# B1653P01Main-2.net
KiCad netlist of a schematic drawn in Altium Designer
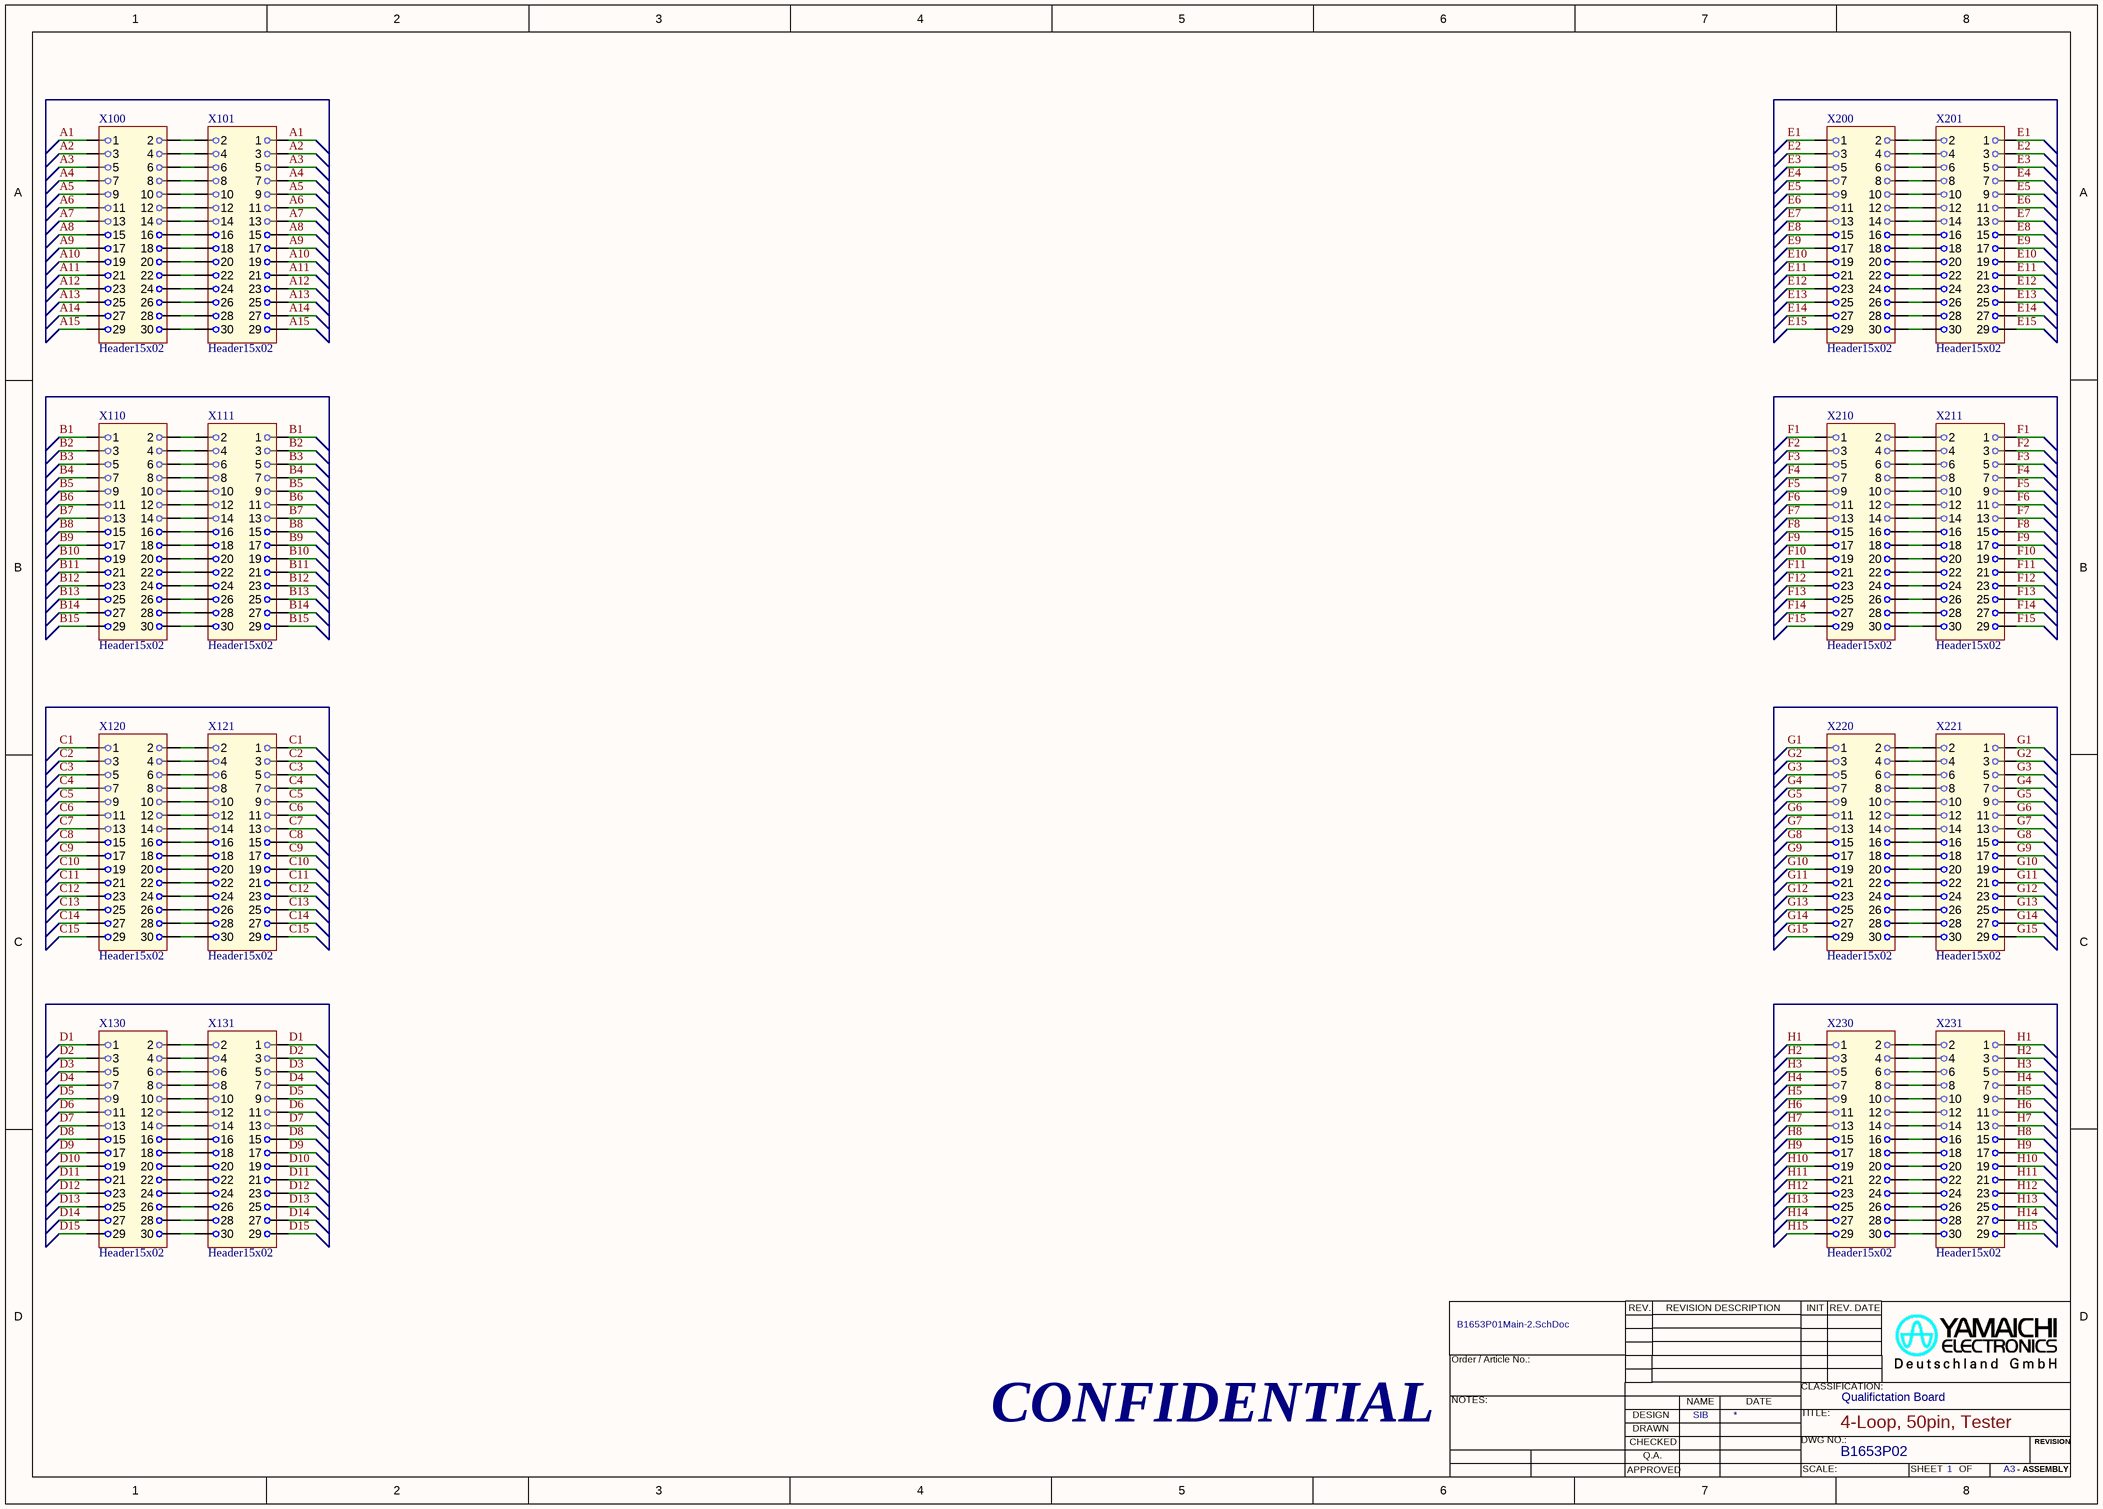
[diagram p0: B1653P01Main-2.SchDoc]

(export (version "E")
  (design (tool "Eeschema 10.0.6"))
  (components
    (comp (ref "X100")
      (value "Header15x02")
      (footprint "HEADER15x02_thru")
      (description "Header15x02 thru")
      (fields (field (name "TYPE") "Header15x02") (field (name "PART NUMBER") "X000027"))
      (libsource (lib "") (part "Header15x02_1"))
    )
    (comp (ref "X101")
      (value "Header15x02")
      (footprint "HEADER15x02_thru")
      (description "Header15x02 thru")
      (fields (field (name "TYPE") "Header15x02") (field (name "PART NUMBER") "X000027"))
      (libsource (lib "X") (part "Header15x02"))
    )
    (comp (ref "X110")
      (value "Header15x02")
      (footprint "HEADER15x02_thru")
      (description "Header15x02 thru")
      (fields (field (name "TYPE") "Header15x02") (field (name "PART NUMBER") "X000027"))
      (libsource (lib "") (part "Header15x02_1"))
    )
    (comp (ref "X111")
      (value "Header15x02")
      (footprint "HEADER15x02_thru")
      (description "Header15x02 thru")
      (fields (field (name "TYPE") "Header15x02") (field (name "PART NUMBER") "X000027"))
      (libsource (lib "X") (part "Header15x02"))
    )
    (comp (ref "X120")
      (value "Header15x02")
      (footprint "HEADER15x02_thru")
      (description "Header15x02 thru")
      (fields (field (name "TYPE") "Header15x02") (field (name "PART NUMBER") "X000027"))
      (libsource (lib "") (part "Header15x02_1"))
    )
    (comp (ref "X121")
      (value "Header15x02")
      (footprint "HEADER15x02_thru")
      (description "Header15x02 thru")
      (fields (field (name "TYPE") "Header15x02") (field (name "PART NUMBER") "X000027"))
      (libsource (lib "X") (part "Header15x02"))
    )
    (comp (ref "X130")
      (value "Header15x02")
      (footprint "HEADER15x02_thru")
      (description "Header15x02 thru")
      (fields (field (name "TYPE") "Header15x02") (field (name "PART NUMBER") "X000027"))
      (libsource (lib "") (part "Header15x02_1"))
    )
    (comp (ref "X131")
      (value "Header15x02")
      (footprint "HEADER15x02_thru")
      (description "Header15x02 thru")
      (fields (field (name "TYPE") "Header15x02") (field (name "PART NUMBER") "X000027"))
      (libsource (lib "X") (part "Header15x02"))
    )
    (comp (ref "X200")
      (value "Header15x02")
      (footprint "HEADER15x02_thru")
      (description "Header15x02 thru")
      (fields (field (name "TYPE") "Header15x02") (field (name "PART NUMBER") "X000027"))
      (libsource (lib "") (part "Header15x02_1"))
    )
    (comp (ref "X201")
      (value "Header15x02")
      (footprint "HEADER15x02_thru")
      (description "Header15x02 thru")
      (fields (field (name "TYPE") "Header15x02") (field (name "PART NUMBER") "X000027"))
      (libsource (lib "X") (part "Header15x02"))
    )
    (comp (ref "X210")
      (value "Header15x02")
      (footprint "HEADER15x02_thru")
      (description "Header15x02 thru")
      (fields (field (name "TYPE") "Header15x02") (field (name "PART NUMBER") "X000027"))
      (libsource (lib "") (part "Header15x02_1"))
    )
    (comp (ref "X211")
      (value "Header15x02")
      (footprint "HEADER15x02_thru")
      (description "Header15x02 thru")
      (fields (field (name "TYPE") "Header15x02") (field (name "PART NUMBER") "X000027"))
      (libsource (lib "X") (part "Header15x02"))
    )
    (comp (ref "X220")
      (value "Header15x02")
      (footprint "HEADER15x02_thru")
      (description "Header15x02 thru")
      (fields (field (name "TYPE") "Header15x02") (field (name "PART NUMBER") "X000027"))
      (libsource (lib "") (part "Header15x02_1"))
    )
    (comp (ref "X221")
      (value "Header15x02")
      (footprint "HEADER15x02_thru")
      (description "Header15x02 thru")
      (fields (field (name "TYPE") "Header15x02") (field (name "PART NUMBER") "X000027"))
      (libsource (lib "X") (part "Header15x02"))
    )
    (comp (ref "X230")
      (value "Header15x02")
      (footprint "HEADER15x02_thru")
      (description "Header15x02 thru")
      (fields (field (name "TYPE") "Header15x02") (field (name "PART NUMBER") "X000027"))
      (libsource (lib "") (part "Header15x02_1"))
    )
    (comp (ref "X231")
      (value "Header15x02")
      (footprint "HEADER15x02_thru")
      (description "Header15x02 thru")
      (fields (field (name "TYPE") "Header15x02") (field (name "PART NUMBER") "X000027"))
      (libsource (lib "X") (part "Header15x02"))
    )
  )
  (nets
    (net (code "1") (name "/A1") (class "Default")
      (node (ref "X100") (pin "1") (pinfunction "1_1") (pintype "passive"))
      (node (ref "X101") (pin "1") (pinfunction "1_1") (pintype "passive"))
    )
    (net (code "2") (name "/A2") (class "Default")
      (node (ref "X100") (pin "3") (pinfunction "3_3") (pintype "passive"))
      (node (ref "X101") (pin "3") (pinfunction "3_3") (pintype "passive"))
    )
    (net (code "3") (name "/A3") (class "Default")
      (node (ref "X100") (pin "5") (pinfunction "5_5") (pintype "passive"))
      (node (ref "X101") (pin "5") (pinfunction "5_5") (pintype "passive"))
    )
    (net (code "4") (name "/A4") (class "Default")
      (node (ref "X100") (pin "7") (pinfunction "7_7") (pintype "passive"))
      (node (ref "X101") (pin "7") (pinfunction "7_7") (pintype "passive"))
    )
    (net (code "5") (name "/A5") (class "Default")
      (node (ref "X100") (pin "9") (pinfunction "9_9") (pintype "passive"))
      (node (ref "X101") (pin "9") (pinfunction "9_9") (pintype "passive"))
    )
    (net (code "6") (name "/A6") (class "Default")
      (node (ref "X100") (pin "11") (pinfunction "11_11") (pintype "passive"))
      (node (ref "X101") (pin "11") (pinfunction "11_11") (pintype "passive"))
    )
    (net (code "7") (name "/A7") (class "Default")
      (node (ref "X100") (pin "13") (pinfunction "13_13") (pintype "passive"))
      (node (ref "X101") (pin "13") (pinfunction "13_13") (pintype "passive"))
    )
    (net (code "8") (name "/A8") (class "Default")
      (node (ref "X100") (pin "15") (pinfunction "15_15") (pintype "passive"))
      (node (ref "X101") (pin "15") (pinfunction "15_15") (pintype "passive"))
    )
    (net (code "9") (name "/A9") (class "Default")
      (node (ref "X100") (pin "17") (pinfunction "17_17") (pintype "passive"))
      (node (ref "X101") (pin "17") (pinfunction "17_17") (pintype "passive"))
    )
    (net (code "10") (name "/A10") (class "Default")
      (node (ref "X100") (pin "19") (pinfunction "19_19") (pintype "passive"))
      (node (ref "X101") (pin "19") (pinfunction "19_19") (pintype "passive"))
    )
    (net (code "11") (name "/A11") (class "Default")
      (node (ref "X100") (pin "21") (pinfunction "21_21") (pintype "passive"))
      (node (ref "X101") (pin "21") (pinfunction "21_21") (pintype "passive"))
    )
    (net (code "12") (name "/A12") (class "Default")
      (node (ref "X100") (pin "23") (pinfunction "23_23") (pintype "passive"))
      (node (ref "X101") (pin "23") (pinfunction "23_23") (pintype "passive"))
    )
    (net (code "13") (name "/A13") (class "Default")
      (node (ref "X100") (pin "25") (pinfunction "25_25") (pintype "passive"))
      (node (ref "X101") (pin "25") (pinfunction "25_25") (pintype "passive"))
    )
    (net (code "14") (name "/A14") (class "Default")
      (node (ref "X100") (pin "27") (pinfunction "27_27") (pintype "passive"))
      (node (ref "X101") (pin "27") (pinfunction "27_27") (pintype "passive"))
    )
    (net (code "15") (name "/A15") (class "Default")
      (node (ref "X100") (pin "29") (pinfunction "29_29") (pintype "passive"))
      (node (ref "X101") (pin "29") (pinfunction "29_29") (pintype "passive"))
    )
    (net (code "16") (name "/B1") (class "Default")
      (node (ref "X110") (pin "1") (pinfunction "1_1") (pintype "passive"))
      (node (ref "X111") (pin "1") (pinfunction "1_1") (pintype "passive"))
    )
    (net (code "17") (name "/B2") (class "Default")
      (node (ref "X110") (pin "3") (pinfunction "3_3") (pintype "passive"))
      (node (ref "X111") (pin "3") (pinfunction "3_3") (pintype "passive"))
    )
    (net (code "18") (name "/B3") (class "Default")
      (node (ref "X110") (pin "5") (pinfunction "5_5") (pintype "passive"))
      (node (ref "X111") (pin "5") (pinfunction "5_5") (pintype "passive"))
    )
    (net (code "19") (name "/B4") (class "Default")
      (node (ref "X110") (pin "7") (pinfunction "7_7") (pintype "passive"))
      (node (ref "X111") (pin "7") (pinfunction "7_7") (pintype "passive"))
    )
    (net (code "20") (name "/B5") (class "Default")
      (node (ref "X110") (pin "9") (pinfunction "9_9") (pintype "passive"))
      (node (ref "X111") (pin "9") (pinfunction "9_9") (pintype "passive"))
    )
    (net (code "21") (name "/B6") (class "Default")
      (node (ref "X110") (pin "11") (pinfunction "11_11") (pintype "passive"))
      (node (ref "X111") (pin "11") (pinfunction "11_11") (pintype "passive"))
    )
    (net (code "22") (name "/B7") (class "Default")
      (node (ref "X110") (pin "13") (pinfunction "13_13") (pintype "passive"))
      (node (ref "X111") (pin "13") (pinfunction "13_13") (pintype "passive"))
    )
    (net (code "23") (name "/B8") (class "Default")
      (node (ref "X110") (pin "15") (pinfunction "15_15") (pintype "passive"))
      (node (ref "X111") (pin "15") (pinfunction "15_15") (pintype "passive"))
    )
    (net (code "24") (name "/B9") (class "Default")
      (node (ref "X110") (pin "17") (pinfunction "17_17") (pintype "passive"))
      (node (ref "X111") (pin "17") (pinfunction "17_17") (pintype "passive"))
    )
    (net (code "25") (name "/B10") (class "Default")
      (node (ref "X110") (pin "19") (pinfunction "19_19") (pintype "passive"))
      (node (ref "X111") (pin "19") (pinfunction "19_19") (pintype "passive"))
    )
    (net (code "26") (name "/B11") (class "Default")
      (node (ref "X110") (pin "21") (pinfunction "21_21") (pintype "passive"))
      (node (ref "X111") (pin "21") (pinfunction "21_21") (pintype "passive"))
    )
    (net (code "27") (name "/B12") (class "Default")
      (node (ref "X110") (pin "23") (pinfunction "23_23") (pintype "passive"))
      (node (ref "X111") (pin "23") (pinfunction "23_23") (pintype "passive"))
    )
    (net (code "28") (name "/B13") (class "Default")
      (node (ref "X110") (pin "25") (pinfunction "25_25") (pintype "passive"))
      (node (ref "X111") (pin "25") (pinfunction "25_25") (pintype "passive"))
    )
    (net (code "29") (name "/B14") (class "Default")
      (node (ref "X110") (pin "27") (pinfunction "27_27") (pintype "passive"))
      (node (ref "X111") (pin "27") (pinfunction "27_27") (pintype "passive"))
    )
    (net (code "30") (name "/B15") (class "Default")
      (node (ref "X110") (pin "29") (pinfunction "29_29") (pintype "passive"))
      (node (ref "X111") (pin "29") (pinfunction "29_29") (pintype "passive"))
    )
    (net (code "31") (name "/C1") (class "Default")
      (node (ref "X120") (pin "1") (pinfunction "1_1") (pintype "passive"))
      (node (ref "X121") (pin "1") (pinfunction "1_1") (pintype "passive"))
    )
    (net (code "32") (name "/C2") (class "Default")
      (node (ref "X120") (pin "3") (pinfunction "3_3") (pintype "passive"))
      (node (ref "X121") (pin "3") (pinfunction "3_3") (pintype "passive"))
    )
    (net (code "33") (name "/C3") (class "Default")
      (node (ref "X120") (pin "5") (pinfunction "5_5") (pintype "passive"))
      (node (ref "X121") (pin "5") (pinfunction "5_5") (pintype "passive"))
    )
    (net (code "34") (name "/C4") (class "Default")
      (node (ref "X120") (pin "7") (pinfunction "7_7") (pintype "passive"))
      (node (ref "X121") (pin "7") (pinfunction "7_7") (pintype "passive"))
    )
    (net (code "35") (name "/C5") (class "Default")
      (node (ref "X120") (pin "9") (pinfunction "9_9") (pintype "passive"))
      (node (ref "X121") (pin "9") (pinfunction "9_9") (pintype "passive"))
    )
    (net (code "36") (name "/C6") (class "Default")
      (node (ref "X120") (pin "11") (pinfunction "11_11") (pintype "passive"))
      (node (ref "X121") (pin "11") (pinfunction "11_11") (pintype "passive"))
    )
    (net (code "37") (name "/C7") (class "Default")
      (node (ref "X120") (pin "13") (pinfunction "13_13") (pintype "passive"))
      (node (ref "X121") (pin "13") (pinfunction "13_13") (pintype "passive"))
    )
    (net (code "38") (name "/C8") (class "Default")
      (node (ref "X120") (pin "15") (pinfunction "15_15") (pintype "passive"))
      (node (ref "X121") (pin "15") (pinfunction "15_15") (pintype "passive"))
    )
    (net (code "39") (name "/C9") (class "Default")
      (node (ref "X120") (pin "17") (pinfunction "17_17") (pintype "passive"))
      (node (ref "X121") (pin "17") (pinfunction "17_17") (pintype "passive"))
    )
    (net (code "40") (name "/C10") (class "Default")
      (node (ref "X120") (pin "19") (pinfunction "19_19") (pintype "passive"))
      (node (ref "X121") (pin "19") (pinfunction "19_19") (pintype "passive"))
    )
    (net (code "41") (name "/C11") (class "Default")
      (node (ref "X120") (pin "21") (pinfunction "21_21") (pintype "passive"))
      (node (ref "X121") (pin "21") (pinfunction "21_21") (pintype "passive"))
    )
    (net (code "42") (name "/C12") (class "Default")
      (node (ref "X120") (pin "23") (pinfunction "23_23") (pintype "passive"))
      (node (ref "X121") (pin "23") (pinfunction "23_23") (pintype "passive"))
    )
    (net (code "43") (name "/C13") (class "Default")
      (node (ref "X120") (pin "25") (pinfunction "25_25") (pintype "passive"))
      (node (ref "X121") (pin "25") (pinfunction "25_25") (pintype "passive"))
    )
    (net (code "44") (name "/C14") (class "Default")
      (node (ref "X120") (pin "27") (pinfunction "27_27") (pintype "passive"))
      (node (ref "X121") (pin "27") (pinfunction "27_27") (pintype "passive"))
    )
    (net (code "45") (name "/C15") (class "Default")
      (node (ref "X120") (pin "29") (pinfunction "29_29") (pintype "passive"))
      (node (ref "X121") (pin "29") (pinfunction "29_29") (pintype "passive"))
    )
    (net (code "46") (name "/D1") (class "Default")
      (node (ref "X130") (pin "1") (pinfunction "1_1") (pintype "passive"))
      (node (ref "X131") (pin "1") (pinfunction "1_1") (pintype "passive"))
    )
    (net (code "47") (name "/D2") (class "Default")
      (node (ref "X130") (pin "3") (pinfunction "3_3") (pintype "passive"))
      (node (ref "X131") (pin "3") (pinfunction "3_3") (pintype "passive"))
    )
    (net (code "48") (name "/D3") (class "Default")
      (node (ref "X130") (pin "5") (pinfunction "5_5") (pintype "passive"))
      (node (ref "X131") (pin "5") (pinfunction "5_5") (pintype "passive"))
    )
    (net (code "49") (name "/D4") (class "Default")
      (node (ref "X130") (pin "7") (pinfunction "7_7") (pintype "passive"))
      (node (ref "X131") (pin "7") (pinfunction "7_7") (pintype "passive"))
    )
    (net (code "50") (name "/D5") (class "Default")
      (node (ref "X130") (pin "9") (pinfunction "9_9") (pintype "passive"))
      (node (ref "X131") (pin "9") (pinfunction "9_9") (pintype "passive"))
    )
    (net (code "51") (name "/D6") (class "Default")
      (node (ref "X130") (pin "11") (pinfunction "11_11") (pintype "passive"))
      (node (ref "X131") (pin "11") (pinfunction "11_11") (pintype "passive"))
    )
    (net (code "52") (name "/D7") (class "Default")
      (node (ref "X130") (pin "13") (pinfunction "13_13") (pintype "passive"))
      (node (ref "X131") (pin "13") (pinfunction "13_13") (pintype "passive"))
    )
    (net (code "53") (name "/D8") (class "Default")
      (node (ref "X130") (pin "15") (pinfunction "15_15") (pintype "passive"))
      (node (ref "X131") (pin "15") (pinfunction "15_15") (pintype "passive"))
    )
    (net (code "54") (name "/D9") (class "Default")
      (node (ref "X130") (pin "17") (pinfunction "17_17") (pintype "passive"))
      (node (ref "X131") (pin "17") (pinfunction "17_17") (pintype "passive"))
    )
    (net (code "55") (name "/D10") (class "Default")
      (node (ref "X130") (pin "19") (pinfunction "19_19") (pintype "passive"))
      (node (ref "X131") (pin "19") (pinfunction "19_19") (pintype "passive"))
    )
    (net (code "56") (name "/D11") (class "Default")
      (node (ref "X130") (pin "21") (pinfunction "21_21") (pintype "passive"))
      (node (ref "X131") (pin "21") (pinfunction "21_21") (pintype "passive"))
    )
    (net (code "57") (name "/D12") (class "Default")
      (node (ref "X130") (pin "23") (pinfunction "23_23") (pintype "passive"))
      (node (ref "X131") (pin "23") (pinfunction "23_23") (pintype "passive"))
    )
    (net (code "58") (name "/D13") (class "Default")
      (node (ref "X130") (pin "25") (pinfunction "25_25") (pintype "passive"))
      (node (ref "X131") (pin "25") (pinfunction "25_25") (pintype "passive"))
    )
    (net (code "59") (name "/D14") (class "Default")
      (node (ref "X130") (pin "27") (pinfunction "27_27") (pintype "passive"))
      (node (ref "X131") (pin "27") (pinfunction "27_27") (pintype "passive"))
    )
    (net (code "60") (name "/D15") (class "Default")
      (node (ref "X130") (pin "29") (pinfunction "29_29") (pintype "passive"))
      (node (ref "X131") (pin "29") (pinfunction "29_29") (pintype "passive"))
    )
    (net (code "61") (name "/E1") (class "Default")
      (node (ref "X200") (pin "1") (pinfunction "1_1") (pintype "passive"))
      (node (ref "X201") (pin "1") (pinfunction "1_1") (pintype "passive"))
    )
    (net (code "62") (name "/E2") (class "Default")
      (node (ref "X200") (pin "3") (pinfunction "3_3") (pintype "passive"))
      (node (ref "X201") (pin "3") (pinfunction "3_3") (pintype "passive"))
    )
    (net (code "63") (name "/E3") (class "Default")
      (node (ref "X200") (pin "5") (pinfunction "5_5") (pintype "passive"))
      (node (ref "X201") (pin "5") (pinfunction "5_5") (pintype "passive"))
    )
    (net (code "64") (name "/E4") (class "Default")
      (node (ref "X200") (pin "7") (pinfunction "7_7") (pintype "passive"))
      (node (ref "X201") (pin "7") (pinfunction "7_7") (pintype "passive"))
    )
    (net (code "65") (name "/E5") (class "Default")
      (node (ref "X200") (pin "9") (pinfunction "9_9") (pintype "passive"))
      (node (ref "X201") (pin "9") (pinfunction "9_9") (pintype "passive"))
    )
    (net (code "66") (name "/E6") (class "Default")
      (node (ref "X200") (pin "11") (pinfunction "11_11") (pintype "passive"))
      (node (ref "X201") (pin "11") (pinfunction "11_11") (pintype "passive"))
    )
    (net (code "67") (name "/E7") (class "Default")
      (node (ref "X200") (pin "13") (pinfunction "13_13") (pintype "passive"))
      (node (ref "X201") (pin "13") (pinfunction "13_13") (pintype "passive"))
    )
    (net (code "68") (name "/E8") (class "Default")
      (node (ref "X200") (pin "15") (pinfunction "15_15") (pintype "passive"))
      (node (ref "X201") (pin "15") (pinfunction "15_15") (pintype "passive"))
    )
    (net (code "69") (name "/E9") (class "Default")
      (node (ref "X200") (pin "17") (pinfunction "17_17") (pintype "passive"))
      (node (ref "X201") (pin "17") (pinfunction "17_17") (pintype "passive"))
    )
    (net (code "70") (name "/E10") (class "Default")
      (node (ref "X200") (pin "19") (pinfunction "19_19") (pintype "passive"))
      (node (ref "X201") (pin "19") (pinfunction "19_19") (pintype "passive"))
    )
    (net (code "71") (name "/E11") (class "Default")
      (node (ref "X200") (pin "21") (pinfunction "21_21") (pintype "passive"))
      (node (ref "X201") (pin "21") (pinfunction "21_21") (pintype "passive"))
    )
    (net (code "72") (name "/E12") (class "Default")
      (node (ref "X200") (pin "23") (pinfunction "23_23") (pintype "passive"))
      (node (ref "X201") (pin "23") (pinfunction "23_23") (pintype "passive"))
    )
    (net (code "73") (name "/E13") (class "Default")
      (node (ref "X200") (pin "25") (pinfunction "25_25") (pintype "passive"))
      (node (ref "X201") (pin "25") (pinfunction "25_25") (pintype "passive"))
    )
    (net (code "74") (name "/E14") (class "Default")
      (node (ref "X200") (pin "27") (pinfunction "27_27") (pintype "passive"))
      (node (ref "X201") (pin "27") (pinfunction "27_27") (pintype "passive"))
    )
    (net (code "75") (name "/E15") (class "Default")
      (node (ref "X200") (pin "29") (pinfunction "29_29") (pintype "passive"))
      (node (ref "X201") (pin "29") (pinfunction "29_29") (pintype "passive"))
    )
    (net (code "76") (name "/F1") (class "Default")
      (node (ref "X210") (pin "1") (pinfunction "1_1") (pintype "passive"))
      (node (ref "X211") (pin "1") (pinfunction "1_1") (pintype "passive"))
    )
    (net (code "77") (name "/F2") (class "Default")
      (node (ref "X210") (pin "3") (pinfunction "3_3") (pintype "passive"))
      (node (ref "X211") (pin "3") (pinfunction "3_3") (pintype "passive"))
    )
    (net (code "78") (name "/F3") (class "Default")
      (node (ref "X210") (pin "5") (pinfunction "5_5") (pintype "passive"))
      (node (ref "X211") (pin "5") (pinfunction "5_5") (pintype "passive"))
    )
    (net (code "79") (name "/F4") (class "Default")
      (node (ref "X210") (pin "7") (pinfunction "7_7") (pintype "passive"))
      (node (ref "X211") (pin "7") (pinfunction "7_7") (pintype "passive"))
    )
    (net (code "80") (name "/F5") (class "Default")
      (node (ref "X210") (pin "9") (pinfunction "9_9") (pintype "passive"))
      (node (ref "X211") (pin "9") (pinfunction "9_9") (pintype "passive"))
    )
    (net (code "81") (name "/F6") (class "Default")
      (node (ref "X210") (pin "11") (pinfunction "11_11") (pintype "passive"))
      (node (ref "X211") (pin "11") (pinfunction "11_11") (pintype "passive"))
    )
    (net (code "82") (name "/F7") (class "Default")
      (node (ref "X210") (pin "13") (pinfunction "13_13") (pintype "passive"))
      (node (ref "X211") (pin "13") (pinfunction "13_13") (pintype "passive"))
    )
    (net (code "83") (name "/F8") (class "Default")
      (node (ref "X210") (pin "15") (pinfunction "15_15") (pintype "passive"))
      (node (ref "X211") (pin "15") (pinfunction "15_15") (pintype "passive"))
    )
    (net (code "84") (name "/F9") (class "Default")
      (node (ref "X210") (pin "17") (pinfunction "17_17") (pintype "passive"))
      (node (ref "X211") (pin "17") (pinfunction "17_17") (pintype "passive"))
    )
    (net (code "85") (name "/F10") (class "Default")
      (node (ref "X210") (pin "19") (pinfunction "19_19") (pintype "passive"))
      (node (ref "X211") (pin "19") (pinfunction "19_19") (pintype "passive"))
    )
    (net (code "86") (name "/F11") (class "Default")
      (node (ref "X210") (pin "21") (pinfunction "21_21") (pintype "passive"))
      (node (ref "X211") (pin "21") (pinfunction "21_21") (pintype "passive"))
    )
    (net (code "87") (name "/F12") (class "Default")
      (node (ref "X210") (pin "23") (pinfunction "23_23") (pintype "passive"))
      (node (ref "X211") (pin "23") (pinfunction "23_23") (pintype "passive"))
    )
    (net (code "88") (name "/F13") (class "Default")
      (node (ref "X210") (pin "25") (pinfunction "25_25") (pintype "passive"))
      (node (ref "X211") (pin "25") (pinfunction "25_25") (pintype "passive"))
    )
    (net (code "89") (name "/F14") (class "Default")
      (node (ref "X210") (pin "27") (pinfunction "27_27") (pintype "passive"))
      (node (ref "X211") (pin "27") (pinfunction "27_27") (pintype "passive"))
    )
    (net (code "90") (name "/F15") (class "Default")
      (node (ref "X210") (pin "29") (pinfunction "29_29") (pintype "passive"))
      (node (ref "X211") (pin "29") (pinfunction "29_29") (pintype "passive"))
    )
    (net (code "91") (name "/G1") (class "Default")
      (node (ref "X220") (pin "1") (pinfunction "1_1") (pintype "passive"))
      (node (ref "X221") (pin "1") (pinfunction "1_1") (pintype "passive"))
    )
    (net (code "92") (name "/G2") (class "Default")
      (node (ref "X220") (pin "3") (pinfunction "3_3") (pintype "passive"))
      (node (ref "X221") (pin "3") (pinfunction "3_3") (pintype "passive"))
    )
    (net (code "93") (name "/G3") (class "Default")
      (node (ref "X220") (pin "5") (pinfunction "5_5") (pintype "passive"))
      (node (ref "X221") (pin "5") (pinfunction "5_5") (pintype "passive"))
    )
    (net (code "94") (name "/G4") (class "Default")
      (node (ref "X220") (pin "7") (pinfunction "7_7") (pintype "passive"))
      (node (ref "X221") (pin "7") (pinfunction "7_7") (pintype "passive"))
    )
    (net (code "95") (name "/G5") (class "Default")
      (node (ref "X220") (pin "9") (pinfunction "9_9") (pintype "passive"))
      (node (ref "X221") (pin "9") (pinfunction "9_9") (pintype "passive"))
    )
    (net (code "96") (name "/G6") (class "Default")
      (node (ref "X220") (pin "11") (pinfunction "11_11") (pintype "passive"))
      (node (ref "X221") (pin "11") (pinfunction "11_11") (pintype "passive"))
    )
    (net (code "97") (name "/G7") (class "Default")
      (node (ref "X220") (pin "13") (pinfunction "13_13") (pintype "passive"))
      (node (ref "X221") (pin "13") (pinfunction "13_13") (pintype "passive"))
    )
    (net (code "98") (name "/G8") (class "Default")
      (node (ref "X220") (pin "15") (pinfunction "15_15") (pintype "passive"))
      (node (ref "X221") (pin "15") (pinfunction "15_15") (pintype "passive"))
    )
    (net (code "99") (name "/G9") (class "Default")
      (node (ref "X220") (pin "17") (pinfunction "17_17") (pintype "passive"))
      (node (ref "X221") (pin "17") (pinfunction "17_17") (pintype "passive"))
    )
    (net (code "100") (name "/G10") (class "Default")
      (node (ref "X220") (pin "19") (pinfunction "19_19") (pintype "passive"))
      (node (ref "X221") (pin "19") (pinfunction "19_19") (pintype "passive"))
    )
    (net (code "101") (name "/G11") (class "Default")
      (node (ref "X220") (pin "21") (pinfunction "21_21") (pintype "passive"))
      (node (ref "X221") (pin "21") (pinfunction "21_21") (pintype "passive"))
    )
    (net (code "102") (name "/G12") (class "Default")
      (node (ref "X220") (pin "23") (pinfunction "23_23") (pintype "passive"))
      (node (ref "X221") (pin "23") (pinfunction "23_23") (pintype "passive"))
    )
    (net (code "103") (name "/G13") (class "Default")
      (node (ref "X220") (pin "25") (pinfunction "25_25") (pintype "passive"))
      (node (ref "X221") (pin "25") (pinfunction "25_25") (pintype "passive"))
    )
    (net (code "104") (name "/G14") (class "Default")
      (node (ref "X220") (pin "27") (pinfunction "27_27") (pintype "passive"))
      (node (ref "X221") (pin "27") (pinfunction "27_27") (pintype "passive"))
    )
    (net (code "105") (name "/G15") (class "Default")
      (node (ref "X220") (pin "29") (pinfunction "29_29") (pintype "passive"))
      (node (ref "X221") (pin "29") (pinfunction "29_29") (pintype "passive"))
    )
    (net (code "106") (name "/H1") (class "Default")
      (node (ref "X230") (pin "1") (pinfunction "1_1") (pintype "passive"))
      (node (ref "X231") (pin "1") (pinfunction "1_1") (pintype "passive"))
    )
    (net (code "107") (name "/H2") (class "Default")
      (node (ref "X230") (pin "3") (pinfunction "3_3") (pintype "passive"))
      (node (ref "X231") (pin "3") (pinfunction "3_3") (pintype "passive"))
    )
    (net (code "108") (name "/H3") (class "Default")
      (node (ref "X230") (pin "5") (pinfunction "5_5") (pintype "passive"))
      (node (ref "X231") (pin "5") (pinfunction "5_5") (pintype "passive"))
    )
    (net (code "109") (name "/H4") (class "Default")
      (node (ref "X230") (pin "7") (pinfunction "7_7") (pintype "passive"))
      (node (ref "X231") (pin "7") (pinfunction "7_7") (pintype "passive"))
    )
    (net (code "110") (name "/H5") (class "Default")
      (node (ref "X230") (pin "9") (pinfunction "9_9") (pintype "passive"))
      (node (ref "X231") (pin "9") (pinfunction "9_9") (pintype "passive"))
    )
    (net (code "111") (name "/H6") (class "Default")
      (node (ref "X230") (pin "11") (pinfunction "11_11") (pintype "passive"))
      (node (ref "X231") (pin "11") (pinfunction "11_11") (pintype "passive"))
    )
    (net (code "112") (name "/H7") (class "Default")
      (node (ref "X230") (pin "13") (pinfunction "13_13") (pintype "passive"))
      (node (ref "X231") (pin "13") (pinfunction "13_13") (pintype "passive"))
    )
    (net (code "113") (name "/H8") (class "Default")
      (node (ref "X230") (pin "15") (pinfunction "15_15") (pintype "passive"))
      (node (ref "X231") (pin "15") (pinfunction "15_15") (pintype "passive"))
    )
    (net (code "114") (name "/H9") (class "Default")
      (node (ref "X230") (pin "17") (pinfunction "17_17") (pintype "passive"))
      (node (ref "X231") (pin "17") (pinfunction "17_17") (pintype "passive"))
    )
    (net (code "115") (name "/H10") (class "Default")
      (node (ref "X230") (pin "19") (pinfunction "19_19") (pintype "passive"))
      (node (ref "X231") (pin "19") (pinfunction "19_19") (pintype "passive"))
    )
    (net (code "116") (name "/H11") (class "Default")
      (node (ref "X230") (pin "21") (pinfunction "21_21") (pintype "passive"))
      (node (ref "X231") (pin "21") (pinfunction "21_21") (pintype "passive"))
    )
    (net (code "117") (name "/H12") (class "Default")
      (node (ref "X230") (pin "23") (pinfunction "23_23") (pintype "passive"))
      (node (ref "X231") (pin "23") (pinfunction "23_23") (pintype "passive"))
    )
    (net (code "118") (name "/H13") (class "Default")
      (node (ref "X230") (pin "25") (pinfunction "25_25") (pintype "passive"))
      (node (ref "X231") (pin "25") (pinfunction "25_25") (pintype "passive"))
    )
    (net (code "119") (name "/H14") (class "Default")
      (node (ref "X230") (pin "27") (pinfunction "27_27") (pintype "passive"))
      (node (ref "X231") (pin "27") (pinfunction "27_27") (pintype "passive"))
    )
    (net (code "120") (name "/H15") (class "Default")
      (node (ref "X230") (pin "29") (pinfunction "29_29") (pintype "passive"))
      (node (ref "X231") (pin "29") (pinfunction "29_29") (pintype "passive"))
    )
    (net (code "121") (name "Net-(X100-Pad2)") (class "Default")
      (node (ref "X100") (pin "2") (pinfunction "2_2") (pintype "passive"))
      (node (ref "X101") (pin "2") (pinfunction "2_2") (pintype "passive"))
    )
    (net (code "122") (name "Net-(X100-Pad4)") (class "Default")
      (node (ref "X100") (pin "4") (pinfunction "4_4") (pintype "passive"))
      (node (ref "X101") (pin "4") (pinfunction "4_4") (pintype "passive"))
    )
    (net (code "123") (name "Net-(X100-Pad6)") (class "Default")
      (node (ref "X100") (pin "6") (pinfunction "6_6") (pintype "passive"))
      (node (ref "X101") (pin "6") (pinfunction "6_6") (pintype "passive"))
    )
    (net (code "124") (name "Net-(X100-Pad8)") (class "Default")
      (node (ref "X100") (pin "8") (pinfunction "8_8") (pintype "passive"))
      (node (ref "X101") (pin "8") (pinfunction "8_8") (pintype "passive"))
    )
    (net (code "125") (name "Net-(X100-Pad10)") (class "Default")
      (node (ref "X100") (pin "10") (pinfunction "10_10") (pintype "passive"))
      (node (ref "X101") (pin "10") (pinfunction "10_10") (pintype "passive"))
    )
    (net (code "126") (name "Net-(X100-Pad12)") (class "Default")
      (node (ref "X100") (pin "12") (pinfunction "12_12") (pintype "passive"))
      (node (ref "X101") (pin "12") (pinfunction "12_12") (pintype "passive"))
    )
    (net (code "127") (name "Net-(X100-Pad14)") (class "Default")
      (node (ref "X100") (pin "14") (pinfunction "14_14") (pintype "passive"))
      (node (ref "X101") (pin "14") (pinfunction "14_14") (pintype "passive"))
    )
    (net (code "128") (name "Net-(X100-Pad16)") (class "Default")
      (node (ref "X100") (pin "16") (pinfunction "16_16") (pintype "passive"))
      (node (ref "X101") (pin "16") (pinfunction "16_16") (pintype "passive"))
    )
    (net (code "129") (name "Net-(X100-Pad18)") (class "Default")
      (node (ref "X100") (pin "18") (pinfunction "18_18") (pintype "passive"))
      (node (ref "X101") (pin "18") (pinfunction "18_18") (pintype "passive"))
    )
    (net (code "130") (name "Net-(X100-Pad20)") (class "Default")
      (node (ref "X100") (pin "20") (pinfunction "20_20") (pintype "passive"))
      (node (ref "X101") (pin "20") (pinfunction "20_20") (pintype "passive"))
    )
    (net (code "131") (name "Net-(X100-Pad22)") (class "Default")
      (node (ref "X100") (pin "22") (pinfunction "22_22") (pintype "passive"))
      (node (ref "X101") (pin "22") (pinfunction "22_22") (pintype "passive"))
    )
    (net (code "132") (name "Net-(X100-Pad24)") (class "Default")
      (node (ref "X100") (pin "24") (pinfunction "24_24") (pintype "passive"))
      (node (ref "X101") (pin "24") (pinfunction "24_24") (pintype "passive"))
    )
    (net (code "133") (name "Net-(X100-Pad26)") (class "Default")
      (node (ref "X100") (pin "26") (pinfunction "26_26") (pintype "passive"))
      (node (ref "X101") (pin "26") (pinfunction "26_26") (pintype "passive"))
    )
    (net (code "134") (name "Net-(X100-Pad28)") (class "Default")
      (node (ref "X100") (pin "28") (pinfunction "28_28") (pintype "passive"))
      (node (ref "X101") (pin "28") (pinfunction "28_28") (pintype "passive"))
    )
    (net (code "135") (name "Net-(X100-Pad30)") (class "Default")
      (node (ref "X100") (pin "30") (pinfunction "30_30") (pintype "passive"))
      (node (ref "X101") (pin "30") (pinfunction "30_30") (pintype "passive"))
    )
    (net (code "136") (name "Net-(X110-Pad2)") (class "Default")
      (node (ref "X110") (pin "2") (pinfunction "2_2") (pintype "passive"))
      (node (ref "X111") (pin "2") (pinfunction "2_2") (pintype "passive"))
    )
    (net (code "137") (name "Net-(X110-Pad4)") (class "Default")
      (node (ref "X110") (pin "4") (pinfunction "4_4") (pintype "passive"))
      (node (ref "X111") (pin "4") (pinfunction "4_4") (pintype "passive"))
    )
    (net (code "138") (name "Net-(X110-Pad6)") (class "Default")
      (node (ref "X110") (pin "6") (pinfunction "6_6") (pintype "passive"))
      (node (ref "X111") (pin "6") (pinfunction "6_6") (pintype "passive"))
    )
    (net (code "139") (name "Net-(X110-Pad8)") (class "Default")
      (node (ref "X110") (pin "8") (pinfunction "8_8") (pintype "passive"))
      (node (ref "X111") (pin "8") (pinfunction "8_8") (pintype "passive"))
    )
    (net (code "140") (name "Net-(X110-Pad10)") (class "Default")
      (node (ref "X110") (pin "10") (pinfunction "10_10") (pintype "passive"))
      (node (ref "X111") (pin "10") (pinfunction "10_10") (pintype "passive"))
    )
    (net (code "141") (name "Net-(X110-Pad12)") (class "Default")
      (node (ref "X110") (pin "12") (pinfunction "12_12") (pintype "passive"))
      (node (ref "X111") (pin "12") (pinfunction "12_12") (pintype "passive"))
    )
    (net (code "142") (name "Net-(X110-Pad14)") (class "Default")
      (node (ref "X110") (pin "14") (pinfunction "14_14") (pintype "passive"))
      (node (ref "X111") (pin "14") (pinfunction "14_14") (pintype "passive"))
    )
    (net (code "143") (name "Net-(X110-Pad16)") (class "Default")
      (node (ref "X110") (pin "16") (pinfunction "16_16") (pintype "passive"))
      (node (ref "X111") (pin "16") (pinfunction "16_16") (pintype "passive"))
    )
    (net (code "144") (name "Net-(X110-Pad18)") (class "Default")
      (node (ref "X110") (pin "18") (pinfunction "18_18") (pintype "passive"))
      (node (ref "X111") (pin "18") (pinfunction "18_18") (pintype "passive"))
    )
    (net (code "145") (name "Net-(X110-Pad20)") (class "Default")
      (node (ref "X110") (pin "20") (pinfunction "20_20") (pintype "passive"))
      (node (ref "X111") (pin "20") (pinfunction "20_20") (pintype "passive"))
    )
    (net (code "146") (name "Net-(X110-Pad22)") (class "Default")
      (node (ref "X110") (pin "22") (pinfunction "22_22") (pintype "passive"))
      (node (ref "X111") (pin "22") (pinfunction "22_22") (pintype "passive"))
    )
    (net (code "147") (name "Net-(X110-Pad24)") (class "Default")
      (node (ref "X110") (pin "24") (pinfunction "24_24") (pintype "passive"))
      (node (ref "X111") (pin "24") (pinfunction "24_24") (pintype "passive"))
    )
    (net (code "148") (name "Net-(X110-Pad26)") (class "Default")
      (node (ref "X110") (pin "26") (pinfunction "26_26") (pintype "passive"))
      (node (ref "X111") (pin "26") (pinfunction "26_26") (pintype "passive"))
    )
    (net (code "149") (name "Net-(X110-Pad28)") (class "Default")
      (node (ref "X110") (pin "28") (pinfunction "28_28") (pintype "passive"))
      (node (ref "X111") (pin "28") (pinfunction "28_28") (pintype "passive"))
    )
    (net (code "150") (name "Net-(X110-Pad30)") (class "Default")
      (node (ref "X110") (pin "30") (pinfunction "30_30") (pintype "passive"))
      (node (ref "X111") (pin "30") (pinfunction "30_30") (pintype "passive"))
    )
    (net (code "151") (name "Net-(X120-Pad2)") (class "Default")
      (node (ref "X120") (pin "2") (pinfunction "2_2") (pintype "passive"))
      (node (ref "X121") (pin "2") (pinfunction "2_2") (pintype "passive"))
    )
    (net (code "152") (name "Net-(X120-Pad4)") (class "Default")
      (node (ref "X120") (pin "4") (pinfunction "4_4") (pintype "passive"))
      (node (ref "X121") (pin "4") (pinfunction "4_4") (pintype "passive"))
    )
    (net (code "153") (name "Net-(X120-Pad6)") (class "Default")
      (node (ref "X120") (pin "6") (pinfunction "6_6") (pintype "passive"))
      (node (ref "X121") (pin "6") (pinfunction "6_6") (pintype "passive"))
    )
    (net (code "154") (name "Net-(X120-Pad8)") (class "Default")
      (node (ref "X120") (pin "8") (pinfunction "8_8") (pintype "passive"))
      (node (ref "X121") (pin "8") (pinfunction "8_8") (pintype "passive"))
    )
    (net (code "155") (name "Net-(X120-Pad10)") (class "Default")
      (node (ref "X120") (pin "10") (pinfunction "10_10") (pintype "passive"))
      (node (ref "X121") (pin "10") (pinfunction "10_10") (pintype "passive"))
    )
    (net (code "156") (name "Net-(X120-Pad12)") (class "Default")
      (node (ref "X120") (pin "12") (pinfunction "12_12") (pintype "passive"))
      (node (ref "X121") (pin "12") (pinfunction "12_12") (pintype "passive"))
    )
    (net (code "157") (name "Net-(X120-Pad14)") (class "Default")
      (node (ref "X120") (pin "14") (pinfunction "14_14") (pintype "passive"))
      (node (ref "X121") (pin "14") (pinfunction "14_14") (pintype "passive"))
    )
    (net (code "158") (name "Net-(X120-Pad16)") (class "Default")
      (node (ref "X120") (pin "16") (pinfunction "16_16") (pintype "passive"))
      (node (ref "X121") (pin "16") (pinfunction "16_16") (pintype "passive"))
    )
    (net (code "159") (name "Net-(X120-Pad18)") (class "Default")
      (node (ref "X120") (pin "18") (pinfunction "18_18") (pintype "passive"))
      (node (ref "X121") (pin "18") (pinfunction "18_18") (pintype "passive"))
    )
    (net (code "160") (name "Net-(X120-Pad20)") (class "Default")
      (node (ref "X120") (pin "20") (pinfunction "20_20") (pintype "passive"))
      (node (ref "X121") (pin "20") (pinfunction "20_20") (pintype "passive"))
    )
    (net (code "161") (name "Net-(X120-Pad22)") (class "Default")
      (node (ref "X120") (pin "22") (pinfunction "22_22") (pintype "passive"))
      (node (ref "X121") (pin "22") (pinfunction "22_22") (pintype "passive"))
    )
    (net (code "162") (name "Net-(X120-Pad24)") (class "Default")
      (node (ref "X120") (pin "24") (pinfunction "24_24") (pintype "passive"))
      (node (ref "X121") (pin "24") (pinfunction "24_24") (pintype "passive"))
    )
    (net (code "163") (name "Net-(X120-Pad26)") (class "Default")
      (node (ref "X120") (pin "26") (pinfunction "26_26") (pintype "passive"))
      (node (ref "X121") (pin "26") (pinfunction "26_26") (pintype "passive"))
    )
    (net (code "164") (name "Net-(X120-Pad28)") (class "Default")
      (node (ref "X120") (pin "28") (pinfunction "28_28") (pintype "passive"))
      (node (ref "X121") (pin "28") (pinfunction "28_28") (pintype "passive"))
    )
    (net (code "165") (name "Net-(X120-Pad30)") (class "Default")
      (node (ref "X120") (pin "30") (pinfunction "30_30") (pintype "passive"))
      (node (ref "X121") (pin "30") (pinfunction "30_30") (pintype "passive"))
    )
    (net (code "166") (name "Net-(X130-Pad2)") (class "Default")
      (node (ref "X130") (pin "2") (pinfunction "2_2") (pintype "passive"))
      (node (ref "X131") (pin "2") (pinfunction "2_2") (pintype "passive"))
    )
    (net (code "167") (name "Net-(X130-Pad4)") (class "Default")
      (node (ref "X130") (pin "4") (pinfunction "4_4") (pintype "passive"))
      (node (ref "X131") (pin "4") (pinfunction "4_4") (pintype "passive"))
    )
    (net (code "168") (name "Net-(X130-Pad6)") (class "Default")
      (node (ref "X130") (pin "6") (pinfunction "6_6") (pintype "passive"))
      (node (ref "X131") (pin "6") (pinfunction "6_6") (pintype "passive"))
    )
    (net (code "169") (name "Net-(X130-Pad8)") (class "Default")
      (node (ref "X130") (pin "8") (pinfunction "8_8") (pintype "passive"))
      (node (ref "X131") (pin "8") (pinfunction "8_8") (pintype "passive"))
    )
    (net (code "170") (name "Net-(X130-Pad10)") (class "Default")
      (node (ref "X130") (pin "10") (pinfunction "10_10") (pintype "passive"))
      (node (ref "X131") (pin "10") (pinfunction "10_10") (pintype "passive"))
    )
    (net (code "171") (name "Net-(X130-Pad12)") (class "Default")
      (node (ref "X130") (pin "12") (pinfunction "12_12") (pintype "passive"))
      (node (ref "X131") (pin "12") (pinfunction "12_12") (pintype "passive"))
    )
    (net (code "172") (name "Net-(X130-Pad14)") (class "Default")
      (node (ref "X130") (pin "14") (pinfunction "14_14") (pintype "passive"))
      (node (ref "X131") (pin "14") (pinfunction "14_14") (pintype "passive"))
    )
    (net (code "173") (name "Net-(X130-Pad16)") (class "Default")
      (node (ref "X130") (pin "16") (pinfunction "16_16") (pintype "passive"))
      (node (ref "X131") (pin "16") (pinfunction "16_16") (pintype "passive"))
    )
    (net (code "174") (name "Net-(X130-Pad18)") (class "Default")
      (node (ref "X130") (pin "18") (pinfunction "18_18") (pintype "passive"))
      (node (ref "X131") (pin "18") (pinfunction "18_18") (pintype "passive"))
    )
    (net (code "175") (name "Net-(X130-Pad20)") (class "Default")
      (node (ref "X130") (pin "20") (pinfunction "20_20") (pintype "passive"))
      (node (ref "X131") (pin "20") (pinfunction "20_20") (pintype "passive"))
    )
    (net (code "176") (name "Net-(X130-Pad22)") (class "Default")
      (node (ref "X130") (pin "22") (pinfunction "22_22") (pintype "passive"))
      (node (ref "X131") (pin "22") (pinfunction "22_22") (pintype "passive"))
    )
    (net (code "177") (name "Net-(X130-Pad24)") (class "Default")
      (node (ref "X130") (pin "24") (pinfunction "24_24") (pintype "passive"))
      (node (ref "X131") (pin "24") (pinfunction "24_24") (pintype "passive"))
    )
    (net (code "178") (name "Net-(X130-Pad26)") (class "Default")
      (node (ref "X130") (pin "26") (pinfunction "26_26") (pintype "passive"))
      (node (ref "X131") (pin "26") (pinfunction "26_26") (pintype "passive"))
    )
    (net (code "179") (name "Net-(X130-Pad28)") (class "Default")
      (node (ref "X130") (pin "28") (pinfunction "28_28") (pintype "passive"))
      (node (ref "X131") (pin "28") (pinfunction "28_28") (pintype "passive"))
    )
    (net (code "180") (name "Net-(X130-Pad30)") (class "Default")
      (node (ref "X130") (pin "30") (pinfunction "30_30") (pintype "passive"))
      (node (ref "X131") (pin "30") (pinfunction "30_30") (pintype "passive"))
    )
    (net (code "181") (name "Net-(X200-Pad2)") (class "Default")
      (node (ref "X200") (pin "2") (pinfunction "2_2") (pintype "passive"))
      (node (ref "X201") (pin "2") (pinfunction "2_2") (pintype "passive"))
    )
    (net (code "182") (name "Net-(X200-Pad4)") (class "Default")
      (node (ref "X200") (pin "4") (pinfunction "4_4") (pintype "passive"))
      (node (ref "X201") (pin "4") (pinfunction "4_4") (pintype "passive"))
    )
    (net (code "183") (name "Net-(X200-Pad6)") (class "Default")
      (node (ref "X200") (pin "6") (pinfunction "6_6") (pintype "passive"))
      (node (ref "X201") (pin "6") (pinfunction "6_6") (pintype "passive"))
    )
    (net (code "184") (name "Net-(X200-Pad8)") (class "Default")
      (node (ref "X200") (pin "8") (pinfunction "8_8") (pintype "passive"))
      (node (ref "X201") (pin "8") (pinfunction "8_8") (pintype "passive"))
    )
    (net (code "185") (name "Net-(X200-Pad10)") (class "Default")
      (node (ref "X200") (pin "10") (pinfunction "10_10") (pintype "passive"))
      (node (ref "X201") (pin "10") (pinfunction "10_10") (pintype "passive"))
    )
    (net (code "186") (name "Net-(X200-Pad12)") (class "Default")
      (node (ref "X200") (pin "12") (pinfunction "12_12") (pintype "passive"))
      (node (ref "X201") (pin "12") (pinfunction "12_12") (pintype "passive"))
    )
    (net (code "187") (name "Net-(X200-Pad14)") (class "Default")
      (node (ref "X200") (pin "14") (pinfunction "14_14") (pintype "passive"))
      (node (ref "X201") (pin "14") (pinfunction "14_14") (pintype "passive"))
    )
    (net (code "188") (name "Net-(X200-Pad16)") (class "Default")
      (node (ref "X200") (pin "16") (pinfunction "16_16") (pintype "passive"))
      (node (ref "X201") (pin "16") (pinfunction "16_16") (pintype "passive"))
    )
    (net (code "189") (name "Net-(X200-Pad18)") (class "Default")
      (node (ref "X200") (pin "18") (pinfunction "18_18") (pintype "passive"))
      (node (ref "X201") (pin "18") (pinfunction "18_18") (pintype "passive"))
    )
    (net (code "190") (name "Net-(X200-Pad20)") (class "Default")
      (node (ref "X200") (pin "20") (pinfunction "20_20") (pintype "passive"))
      (node (ref "X201") (pin "20") (pinfunction "20_20") (pintype "passive"))
    )
    (net (code "191") (name "Net-(X200-Pad22)") (class "Default")
      (node (ref "X200") (pin "22") (pinfunction "22_22") (pintype "passive"))
      (node (ref "X201") (pin "22") (pinfunction "22_22") (pintype "passive"))
    )
    (net (code "192") (name "Net-(X200-Pad24)") (class "Default")
      (node (ref "X200") (pin "24") (pinfunction "24_24") (pintype "passive"))
      (node (ref "X201") (pin "24") (pinfunction "24_24") (pintype "passive"))
    )
    (net (code "193") (name "Net-(X200-Pad26)") (class "Default")
      (node (ref "X200") (pin "26") (pinfunction "26_26") (pintype "passive"))
      (node (ref "X201") (pin "26") (pinfunction "26_26") (pintype "passive"))
    )
    (net (code "194") (name "Net-(X200-Pad28)") (class "Default")
      (node (ref "X200") (pin "28") (pinfunction "28_28") (pintype "passive"))
      (node (ref "X201") (pin "28") (pinfunction "28_28") (pintype "passive"))
    )
    (net (code "195") (name "Net-(X200-Pad30)") (class "Default")
      (node (ref "X200") (pin "30") (pinfunction "30_30") (pintype "passive"))
      (node (ref "X201") (pin "30") (pinfunction "30_30") (pintype "passive"))
    )
    (net (code "196") (name "Net-(X210-Pad2)") (class "Default")
      (node (ref "X210") (pin "2") (pinfunction "2_2") (pintype "passive"))
      (node (ref "X211") (pin "2") (pinfunction "2_2") (pintype "passive"))
    )
    (net (code "197") (name "Net-(X210-Pad4)") (class "Default")
      (node (ref "X210") (pin "4") (pinfunction "4_4") (pintype "passive"))
      (node (ref "X211") (pin "4") (pinfunction "4_4") (pintype "passive"))
    )
    (net (code "198") (name "Net-(X210-Pad6)") (class "Default")
      (node (ref "X210") (pin "6") (pinfunction "6_6") (pintype "passive"))
      (node (ref "X211") (pin "6") (pinfunction "6_6") (pintype "passive"))
    )
    (net (code "199") (name "Net-(X210-Pad8)") (class "Default")
      (node (ref "X210") (pin "8") (pinfunction "8_8") (pintype "passive"))
      (node (ref "X211") (pin "8") (pinfunction "8_8") (pintype "passive"))
    )
    (net (code "200") (name "Net-(X210-Pad10)") (class "Default")
      (node (ref "X210") (pin "10") (pinfunction "10_10") (pintype "passive"))
      (node (ref "X211") (pin "10") (pinfunction "10_10") (pintype "passive"))
    )
    (net (code "201") (name "Net-(X210-Pad12)") (class "Default")
      (node (ref "X210") (pin "12") (pinfunction "12_12") (pintype "passive"))
      (node (ref "X211") (pin "12") (pinfunction "12_12") (pintype "passive"))
    )
    (net (code "202") (name "Net-(X210-Pad14)") (class "Default")
      (node (ref "X210") (pin "14") (pinfunction "14_14") (pintype "passive"))
      (node (ref "X211") (pin "14") (pinfunction "14_14") (pintype "passive"))
    )
    (net (code "203") (name "Net-(X210-Pad16)") (class "Default")
      (node (ref "X210") (pin "16") (pinfunction "16_16") (pintype "passive"))
      (node (ref "X211") (pin "16") (pinfunction "16_16") (pintype "passive"))
    )
    (net (code "204") (name "Net-(X210-Pad18)") (class "Default")
      (node (ref "X210") (pin "18") (pinfunction "18_18") (pintype "passive"))
      (node (ref "X211") (pin "18") (pinfunction "18_18") (pintype "passive"))
    )
    (net (code "205") (name "Net-(X210-Pad20)") (class "Default")
      (node (ref "X210") (pin "20") (pinfunction "20_20") (pintype "passive"))
      (node (ref "X211") (pin "20") (pinfunction "20_20") (pintype "passive"))
    )
    (net (code "206") (name "Net-(X210-Pad22)") (class "Default")
      (node (ref "X210") (pin "22") (pinfunction "22_22") (pintype "passive"))
      (node (ref "X211") (pin "22") (pinfunction "22_22") (pintype "passive"))
    )
    (net (code "207") (name "Net-(X210-Pad24)") (class "Default")
      (node (ref "X210") (pin "24") (pinfunction "24_24") (pintype "passive"))
      (node (ref "X211") (pin "24") (pinfunction "24_24") (pintype "passive"))
    )
    (net (code "208") (name "Net-(X210-Pad26)") (class "Default")
      (node (ref "X210") (pin "26") (pinfunction "26_26") (pintype "passive"))
      (node (ref "X211") (pin "26") (pinfunction "26_26") (pintype "passive"))
    )
    (net (code "209") (name "Net-(X210-Pad28)") (class "Default")
      (node (ref "X210") (pin "28") (pinfunction "28_28") (pintype "passive"))
      (node (ref "X211") (pin "28") (pinfunction "28_28") (pintype "passive"))
    )
    (net (code "210") (name "Net-(X210-Pad30)") (class "Default")
      (node (ref "X210") (pin "30") (pinfunction "30_30") (pintype "passive"))
      (node (ref "X211") (pin "30") (pinfunction "30_30") (pintype "passive"))
    )
    (net (code "211") (name "Net-(X220-Pad2)") (class "Default")
      (node (ref "X220") (pin "2") (pinfunction "2_2") (pintype "passive"))
      (node (ref "X221") (pin "2") (pinfunction "2_2") (pintype "passive"))
    )
    (net (code "212") (name "Net-(X220-Pad4)") (class "Default")
      (node (ref "X220") (pin "4") (pinfunction "4_4") (pintype "passive"))
      (node (ref "X221") (pin "4") (pinfunction "4_4") (pintype "passive"))
    )
    (net (code "213") (name "Net-(X220-Pad6)") (class "Default")
      (node (ref "X220") (pin "6") (pinfunction "6_6") (pintype "passive"))
      (node (ref "X221") (pin "6") (pinfunction "6_6") (pintype "passive"))
    )
    (net (code "214") (name "Net-(X220-Pad8)") (class "Default")
      (node (ref "X220") (pin "8") (pinfunction "8_8") (pintype "passive"))
      (node (ref "X221") (pin "8") (pinfunction "8_8") (pintype "passive"))
    )
    (net (code "215") (name "Net-(X220-Pad10)") (class "Default")
      (node (ref "X220") (pin "10") (pinfunction "10_10") (pintype "passive"))
      (node (ref "X221") (pin "10") (pinfunction "10_10") (pintype "passive"))
    )
    (net (code "216") (name "Net-(X220-Pad12)") (class "Default")
      (node (ref "X220") (pin "12") (pinfunction "12_12") (pintype "passive"))
      (node (ref "X221") (pin "12") (pinfunction "12_12") (pintype "passive"))
    )
    (net (code "217") (name "Net-(X220-Pad14)") (class "Default")
      (node (ref "X220") (pin "14") (pinfunction "14_14") (pintype "passive"))
      (node (ref "X221") (pin "14") (pinfunction "14_14") (pintype "passive"))
    )
    (net (code "218") (name "Net-(X220-Pad16)") (class "Default")
      (node (ref "X220") (pin "16") (pinfunction "16_16") (pintype "passive"))
      (node (ref "X221") (pin "16") (pinfunction "16_16") (pintype "passive"))
    )
    (net (code "219") (name "Net-(X220-Pad18)") (class "Default")
      (node (ref "X220") (pin "18") (pinfunction "18_18") (pintype "passive"))
      (node (ref "X221") (pin "18") (pinfunction "18_18") (pintype "passive"))
    )
    (net (code "220") (name "Net-(X220-Pad20)") (class "Default")
      (node (ref "X220") (pin "20") (pinfunction "20_20") (pintype "passive"))
      (node (ref "X221") (pin "20") (pinfunction "20_20") (pintype "passive"))
    )
    (net (code "221") (name "Net-(X220-Pad22)") (class "Default")
      (node (ref "X220") (pin "22") (pinfunction "22_22") (pintype "passive"))
      (node (ref "X221") (pin "22") (pinfunction "22_22") (pintype "passive"))
    )
    (net (code "222") (name "Net-(X220-Pad24)") (class "Default")
      (node (ref "X220") (pin "24") (pinfunction "24_24") (pintype "passive"))
      (node (ref "X221") (pin "24") (pinfunction "24_24") (pintype "passive"))
    )
    (net (code "223") (name "Net-(X220-Pad26)") (class "Default")
      (node (ref "X220") (pin "26") (pinfunction "26_26") (pintype "passive"))
      (node (ref "X221") (pin "26") (pinfunction "26_26") (pintype "passive"))
    )
    (net (code "224") (name "Net-(X220-Pad28)") (class "Default")
      (node (ref "X220") (pin "28") (pinfunction "28_28") (pintype "passive"))
      (node (ref "X221") (pin "28") (pinfunction "28_28") (pintype "passive"))
    )
    (net (code "225") (name "Net-(X220-Pad30)") (class "Default")
      (node (ref "X220") (pin "30") (pinfunction "30_30") (pintype "passive"))
      (node (ref "X221") (pin "30") (pinfunction "30_30") (pintype "passive"))
    )
    (net (code "226") (name "Net-(X230-Pad2)") (class "Default")
      (node (ref "X230") (pin "2") (pinfunction "2_2") (pintype "passive"))
      (node (ref "X231") (pin "2") (pinfunction "2_2") (pintype "passive"))
    )
    (net (code "227") (name "Net-(X230-Pad4)") (class "Default")
      (node (ref "X230") (pin "4") (pinfunction "4_4") (pintype "passive"))
      (node (ref "X231") (pin "4") (pinfunction "4_4") (pintype "passive"))
    )
    (net (code "228") (name "Net-(X230-Pad6)") (class "Default")
      (node (ref "X230") (pin "6") (pinfunction "6_6") (pintype "passive"))
      (node (ref "X231") (pin "6") (pinfunction "6_6") (pintype "passive"))
    )
    (net (code "229") (name "Net-(X230-Pad8)") (class "Default")
      (node (ref "X230") (pin "8") (pinfunction "8_8") (pintype "passive"))
      (node (ref "X231") (pin "8") (pinfunction "8_8") (pintype "passive"))
    )
    (net (code "230") (name "Net-(X230-Pad10)") (class "Default")
      (node (ref "X230") (pin "10") (pinfunction "10_10") (pintype "passive"))
      (node (ref "X231") (pin "10") (pinfunction "10_10") (pintype "passive"))
    )
    (net (code "231") (name "Net-(X230-Pad12)") (class "Default")
      (node (ref "X230") (pin "12") (pinfunction "12_12") (pintype "passive"))
      (node (ref "X231") (pin "12") (pinfunction "12_12") (pintype "passive"))
    )
    (net (code "232") (name "Net-(X230-Pad14)") (class "Default")
      (node (ref "X230") (pin "14") (pinfunction "14_14") (pintype "passive"))
      (node (ref "X231") (pin "14") (pinfunction "14_14") (pintype "passive"))
    )
    (net (code "233") (name "Net-(X230-Pad16)") (class "Default")
      (node (ref "X230") (pin "16") (pinfunction "16_16") (pintype "passive"))
      (node (ref "X231") (pin "16") (pinfunction "16_16") (pintype "passive"))
    )
    (net (code "234") (name "Net-(X230-Pad18)") (class "Default")
      (node (ref "X230") (pin "18") (pinfunction "18_18") (pintype "passive"))
      (node (ref "X231") (pin "18") (pinfunction "18_18") (pintype "passive"))
    )
    (net (code "235") (name "Net-(X230-Pad20)") (class "Default")
      (node (ref "X230") (pin "20") (pinfunction "20_20") (pintype "passive"))
      (node (ref "X231") (pin "20") (pinfunction "20_20") (pintype "passive"))
    )
    (net (code "236") (name "Net-(X230-Pad22)") (class "Default")
      (node (ref "X230") (pin "22") (pinfunction "22_22") (pintype "passive"))
      (node (ref "X231") (pin "22") (pinfunction "22_22") (pintype "passive"))
    )
    (net (code "237") (name "Net-(X230-Pad24)") (class "Default")
      (node (ref "X230") (pin "24") (pinfunction "24_24") (pintype "passive"))
      (node (ref "X231") (pin "24") (pinfunction "24_24") (pintype "passive"))
    )
    (net (code "238") (name "Net-(X230-Pad26)") (class "Default")
      (node (ref "X230") (pin "26") (pinfunction "26_26") (pintype "passive"))
      (node (ref "X231") (pin "26") (pinfunction "26_26") (pintype "passive"))
    )
    (net (code "239") (name "Net-(X230-Pad28)") (class "Default")
      (node (ref "X230") (pin "28") (pinfunction "28_28") (pintype "passive"))
      (node (ref "X231") (pin "28") (pinfunction "28_28") (pintype "passive"))
    )
    (net (code "240") (name "Net-(X230-Pad30)") (class "Default")
      (node (ref "X230") (pin "30") (pinfunction "30_30") (pintype "passive"))
      (node (ref "X231") (pin "30") (pinfunction "30_30") (pintype "passive"))
    )
  )
)
